# 04B-340.net
KiCad netlist of a schematic drawn in EAGLE
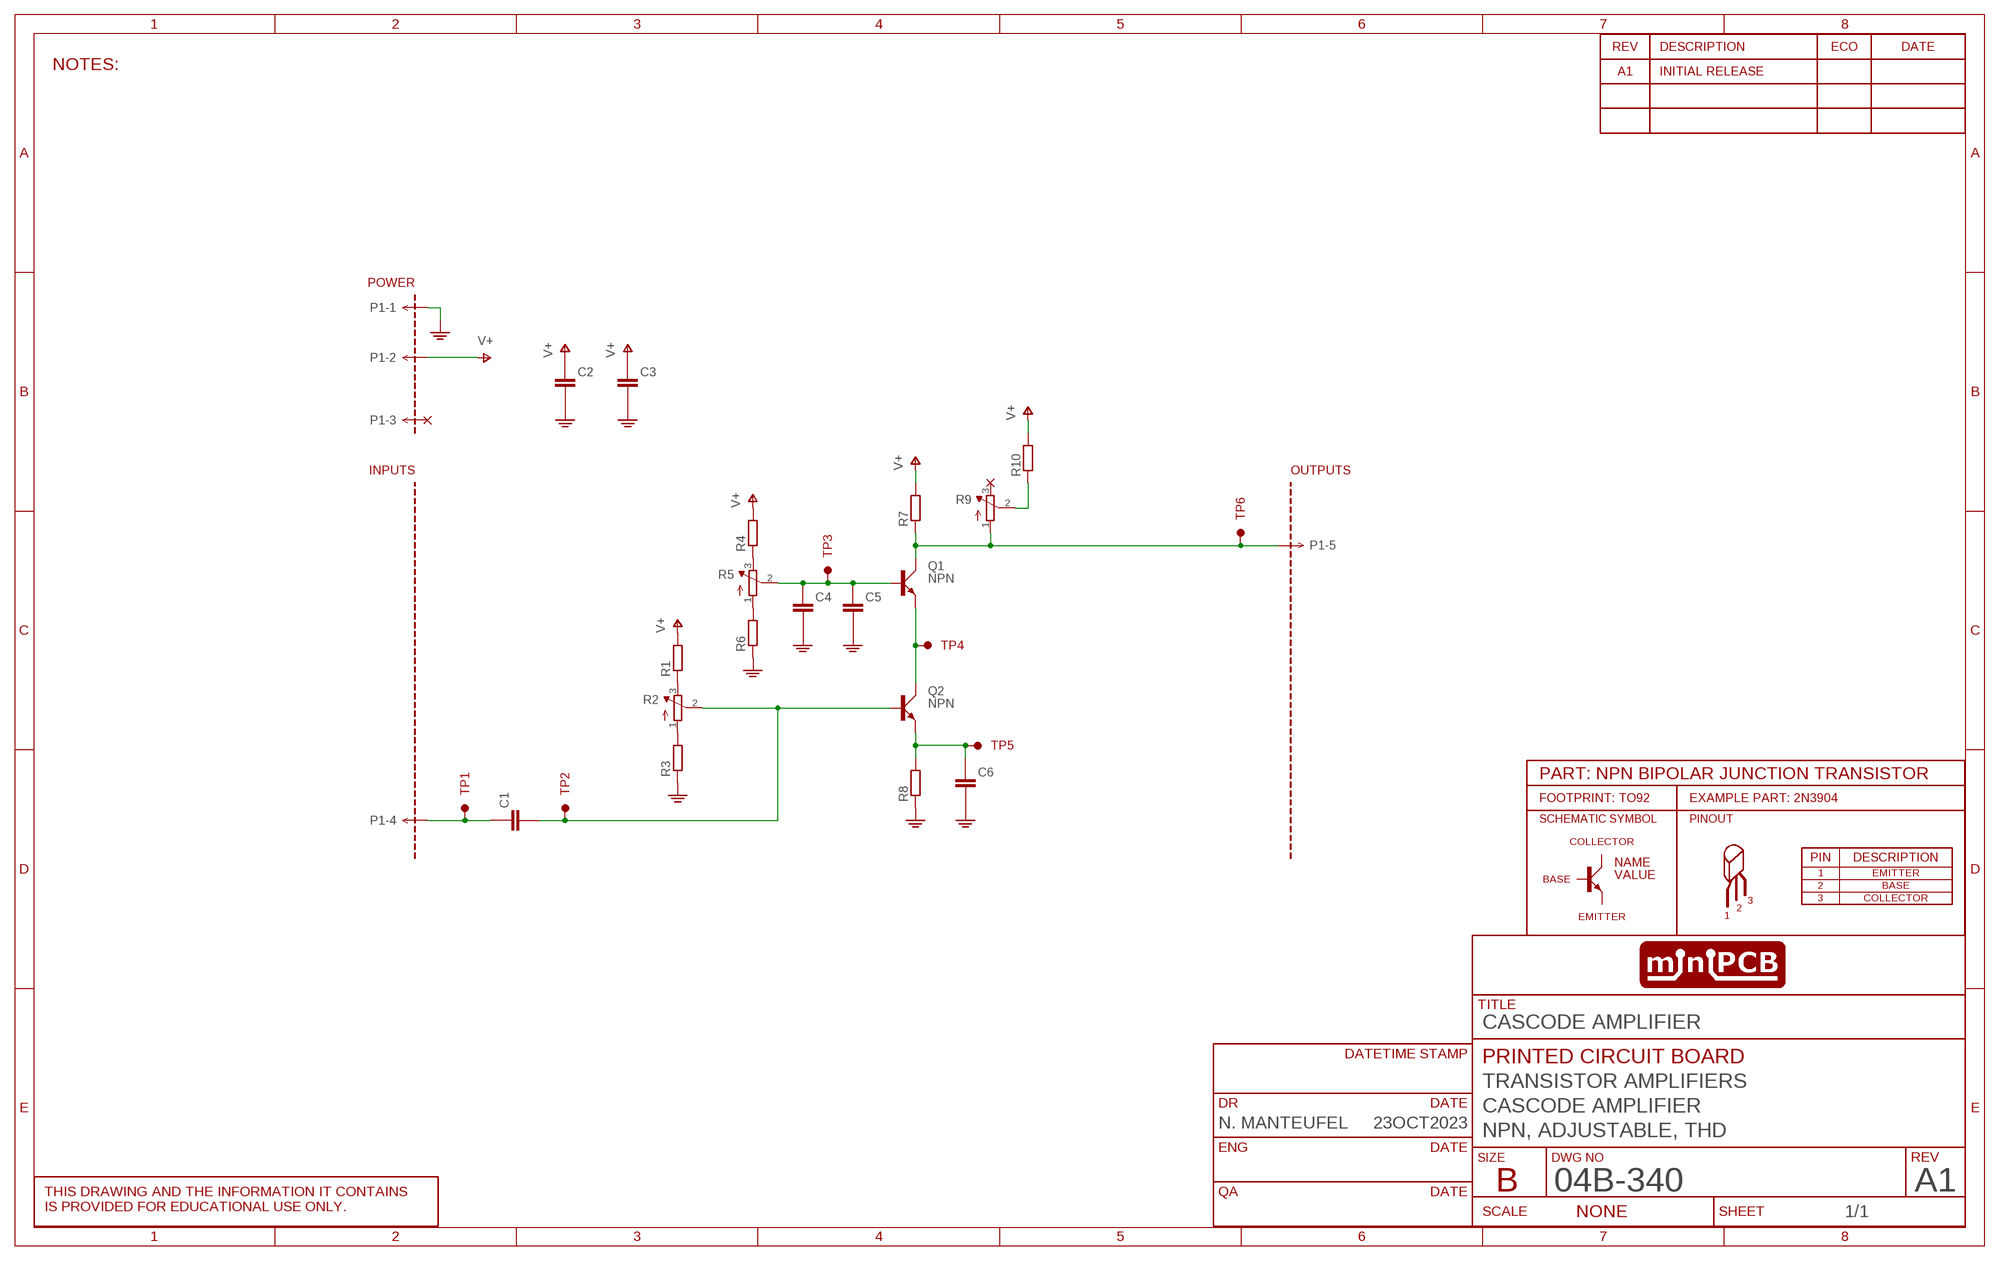
[diagram p0: schematic, sheet 1]

(export (version "E")
  (design (tool "Eeschema 10.0.6"))
  (components
    (comp (ref "C1")
      (value "CAPACITORTHD")
      (footprint "eagle-import:C050-024X044")
      (libsource (lib "eagle-import") (part "CAPACITORTHD"))
    )
    (comp (ref "C2")
      (value "CAPACITOR_10")
      (footprint "eagle-import:C5MM")
      (libsource (lib "eagle-import") (part "CAPACITOR_10"))
    )
    (comp (ref "C3")
      (value "CAPACITORTHD")
      (footprint "eagle-import:C050-024X044")
      (libsource (lib "eagle-import") (part "CAPACITORTHD"))
    )
    (comp (ref "C4")
      (value "CAPACITORTHD")
      (footprint "eagle-import:C050-024X044")
      (libsource (lib "eagle-import") (part "CAPACITORTHD"))
    )
    (comp (ref "C5")
      (value "CAPACITOR_10")
      (footprint "eagle-import:C5MM")
      (libsource (lib "eagle-import") (part "CAPACITOR_10"))
    )
    (comp (ref "C6")
      (value "CAPACITOR_10")
      (footprint "eagle-import:C5MM")
      (libsource (lib "eagle-import") (part "CAPACITOR_10"))
    )
    (comp (ref "P1")
      (value "MINIPCB_5P5P")
      (footprint "eagle-import:PINS_1X5")
      (libsource (lib "eagle-import") (part "MINIPCB_5P5P"))
    )
    (comp (ref "PCB1")
      (value "MINIPCB_0P50X50")
      (footprint "eagle-import:MINIPCB_0P_50X50MM")
      (fields
        (field (name "CIRCUIT_CATEGORY") "TRANSISTOR AMPLIFIERS")
        (field (name "PART_NUMBER") "04B-340")
        (field (name "REVISION") "A1-01")
        (field (name "TITLE") "CASCODE AMPLIFIER")
      )
      (libsource (lib "eagle-import") (part "MINIPCB_0P50X50"))
    )
    (comp (ref "Q1")
      (value "NPN")
      (footprint "eagle-import:TO92-EBC-OVAL")
      (libsource (lib "eagle-import") (part "BJT_NPNEBC"))
    )
    (comp (ref "Q2")
      (value "NPN")
      (footprint "eagle-import:TO92-EBC-OVAL")
      (libsource (lib "eagle-import") (part "BJT_NPNEBC"))
    )
    (comp (ref "R1")
      (value "RESISTORTHD")
      (footprint "eagle-import:0204_10")
      (libsource (lib "eagle-import") (part "RESISTORTHD"))
    )
    (comp (ref "R2")
      (value "TRIMPOT0.100THD")
      (footprint "eagle-import:TRIM_0100")
      (libsource (lib "eagle-import") (part "TRIMPOT0.100THD"))
    )
    (comp (ref "R3")
      (value "RESISTORTHD")
      (footprint "eagle-import:0204_10")
      (libsource (lib "eagle-import") (part "RESISTORTHD"))
    )
    (comp (ref "R4")
      (value "RESISTORTHD")
      (footprint "eagle-import:0204_10")
      (libsource (lib "eagle-import") (part "RESISTORTHD"))
    )
    (comp (ref "R5")
      (value "TRIMPOT0.100THD")
      (footprint "eagle-import:TRIM_0100")
      (libsource (lib "eagle-import") (part "TRIMPOT0.100THD"))
    )
    (comp (ref "R6")
      (value "RESISTORTHD")
      (footprint "eagle-import:0204_10")
      (libsource (lib "eagle-import") (part "RESISTORTHD"))
    )
    (comp (ref "R7")
      (value "RESISTORTHD")
      (footprint "eagle-import:0204_10")
      (libsource (lib "eagle-import") (part "RESISTORTHD"))
    )
    (comp (ref "R8")
      (value "RESISTORTHD")
      (footprint "eagle-import:0204_10")
      (libsource (lib "eagle-import") (part "RESISTORTHD"))
    )
    (comp (ref "R9")
      (value "TRIMPOT0.100THD")
      (footprint "eagle-import:TRIM_0100")
      (libsource (lib "eagle-import") (part "TRIMPOT0.100THD"))
    )
    (comp (ref "R10")
      (value "RESISTORTHD")
      (footprint "eagle-import:0204_10")
      (libsource (lib "eagle-import") (part "RESISTORTHD"))
    )
    (comp (ref "TP1")
      (value "TESTPOINTKE5000-SMTEXT")
      (footprint "eagle-import:PINS_1_TESTPOINT_KE5000_NOTEXT")
      (libsource (lib "eagle-import") (part "TESTPOINTKE5000-SMTEXT"))
    )
    (comp (ref "TP2")
      (value "TESTPOINTKE5000-SMTEXT")
      (footprint "eagle-import:PINS_1_TESTPOINT_KE5000_NOTEXT")
      (libsource (lib "eagle-import") (part "TESTPOINTKE5000-SMTEXT"))
    )
    (comp (ref "TP3")
      (value "TESTPOINTKE5000-SMTEXT")
      (footprint "eagle-import:PINS_1_TESTPOINT_KE5000_NOTEXT")
      (libsource (lib "eagle-import") (part "TESTPOINTKE5000-SMTEXT"))
    )
    (comp (ref "TP4")
      (value "TESTPOINTKE5000-SMTEXT")
      (footprint "eagle-import:PINS_1_TESTPOINT_KE5000_NOTEXT")
      (libsource (lib "eagle-import") (part "TESTPOINTKE5000-SMTEXT"))
    )
    (comp (ref "TP5")
      (value "TESTPOINTKE5000-SMTEXT")
      (footprint "eagle-import:PINS_1_TESTPOINT_KE5000_NOTEXT")
      (libsource (lib "eagle-import") (part "TESTPOINTKE5000-SMTEXT"))
    )
    (comp (ref "TP6")
      (value "TESTPOINTKE5000-SMTEXT")
      (footprint "eagle-import:PINS_1_TESTPOINT_KE5000_NOTEXT")
      (libsource (lib "eagle-import") (part "TESTPOINTKE5000-SMTEXT"))
    )
  )
  (nets
    (net (code "1") (name "GND") (class "Default")
      (node (ref "C2") (pin "-") (pinfunction "-_-") (pintype "passive"))
      (node (ref "C3") (pin "2") (pinfunction "-_2") (pintype "passive"))
      (node (ref "C4") (pin "2") (pinfunction "-_2") (pintype "passive"))
      (node (ref "C5") (pin "-") (pinfunction "-_-") (pintype "passive"))
      (node (ref "C6") (pin "-") (pinfunction "-_-") (pintype "passive"))
      (node (ref "P1") (pin "1") (pinfunction "1_1") (pintype "bidirectional"))
      (node (ref "R3") (pin "1") (pinfunction "1_1") (pintype "passive"))
      (node (ref "R6") (pin "1") (pinfunction "1_1") (pintype "passive"))
      (node (ref "R8") (pin "1") (pinfunction "1_1") (pintype "passive"))
    )
    (net (code "2") (name "Net-(C1-+)") (class "Default")
      (node (ref "C1") (pin "1") (pinfunction "+_1") (pintype "passive"))
      (node (ref "P1") (pin "4") (pinfunction "1_4") (pintype "bidirectional"))
      (node (ref "TP1") (pin "1") (pinfunction "1_1") (pintype "bidirectional"))
    )
    (net (code "3") (name "Net-(C1--)") (class "Default")
      (node (ref "C1") (pin "2") (pinfunction "-_2") (pintype "passive"))
      (node (ref "Q2") (pin "B") (pinfunction "B_B") (pintype "passive"))
      (node (ref "R2") (pin "2") (pinfunction "S_2") (pintype "passive"))
      (node (ref "TP2") (pin "1") (pinfunction "1_1") (pintype "bidirectional"))
    )
    (net (code "4") (name "Net-(C4-+)") (class "Default")
      (node (ref "C4") (pin "1") (pinfunction "+_1") (pintype "passive"))
      (node (ref "C5") (pin "+") (pinfunction "+_+") (pintype "passive"))
      (node (ref "Q1") (pin "B") (pinfunction "B_B") (pintype "passive"))
      (node (ref "R5") (pin "2") (pinfunction "S_2") (pintype "passive"))
      (node (ref "TP3") (pin "1") (pinfunction "1_1") (pintype "bidirectional"))
    )
    (net (code "5") (name "Net-(C6-Pad+)") (class "Default")
      (node (ref "C6") (pin "+") (pinfunction "+_+") (pintype "passive"))
      (node (ref "Q2") (pin "E") (pinfunction "E_E") (pintype "passive"))
      (node (ref "R8") (pin "2") (pinfunction "2_2") (pintype "passive"))
      (node (ref "TP5") (pin "1") (pinfunction "1_1") (pintype "bidirectional"))
    )
    (net (code "6") (name "Net-(P1E-1)") (class "Default")
      (node (ref "P1") (pin "5") (pinfunction "1_5") (pintype "bidirectional"))
      (node (ref "Q1") (pin "C") (pinfunction "C_C") (pintype "passive"))
      (node (ref "R7") (pin "1") (pinfunction "1_1") (pintype "passive"))
      (node (ref "R9") (pin "1") (pinfunction "A_1") (pintype "passive"))
      (node (ref "TP6") (pin "1") (pinfunction "1_1") (pintype "bidirectional"))
    )
    (net (code "7") (name "Net-(Q1-PadE)") (class "Default")
      (node (ref "Q1") (pin "E") (pinfunction "E_E") (pintype "passive"))
      (node (ref "Q2") (pin "C") (pinfunction "C_C") (pintype "passive"))
      (node (ref "TP4") (pin "1") (pinfunction "1_1") (pintype "bidirectional"))
    )
    (net (code "8") (name "Net-(R2-A)") (class "Default")
      (node (ref "R2") (pin "1") (pinfunction "A_1") (pintype "passive"))
      (node (ref "R3") (pin "2") (pinfunction "2_2") (pintype "passive"))
    )
    (net (code "9") (name "Net-(R2-E)") (class "Default")
      (node (ref "R1") (pin "1") (pinfunction "1_1") (pintype "passive"))
      (node (ref "R2") (pin "3") (pinfunction "E_3") (pintype "passive"))
    )
    (net (code "10") (name "Net-(R5-A)") (class "Default")
      (node (ref "R5") (pin "1") (pinfunction "A_1") (pintype "passive"))
      (node (ref "R6") (pin "2") (pinfunction "2_2") (pintype "passive"))
    )
    (net (code "11") (name "Net-(R5-E)") (class "Default")
      (node (ref "R4") (pin "1") (pinfunction "1_1") (pintype "passive"))
      (node (ref "R5") (pin "3") (pinfunction "E_3") (pintype "passive"))
    )
    (net (code "12") (name "Net-(R9-S)") (class "Default")
      (node (ref "R10") (pin "1") (pinfunction "1_1") (pintype "passive"))
      (node (ref "R9") (pin "2") (pinfunction "S_2") (pintype "passive"))
    )
    (net (code "13") (name "V+") (class "Default")
      (node (ref "C2") (pin "+") (pinfunction "+_+") (pintype "passive"))
      (node (ref "C3") (pin "1") (pinfunction "+_1") (pintype "passive"))
      (node (ref "P1") (pin "2") (pinfunction "1_2") (pintype "bidirectional"))
      (node (ref "R1") (pin "2") (pinfunction "2_2") (pintype "passive"))
      (node (ref "R10") (pin "2") (pinfunction "2_2") (pintype "passive"))
      (node (ref "R4") (pin "2") (pinfunction "2_2") (pintype "passive"))
      (node (ref "R7") (pin "2") (pinfunction "2_2") (pintype "passive"))
    )
    (net (code "14") (name "unconnected-(P1C-1-Pad3)") (class "Default")
      (node (ref "P1") (pin "3") (pinfunction "1_3") (pintype "bidirectional"))
    )
    (net (code "15") (name "unconnected-(R9-E-Pad3)") (class "Default")
      (node (ref "R9") (pin "3") (pinfunction "E_3") (pintype "passive"))
    )
  )
)
